# rpm.net
KiCad netlist of a schematic drawn in Altium Designer
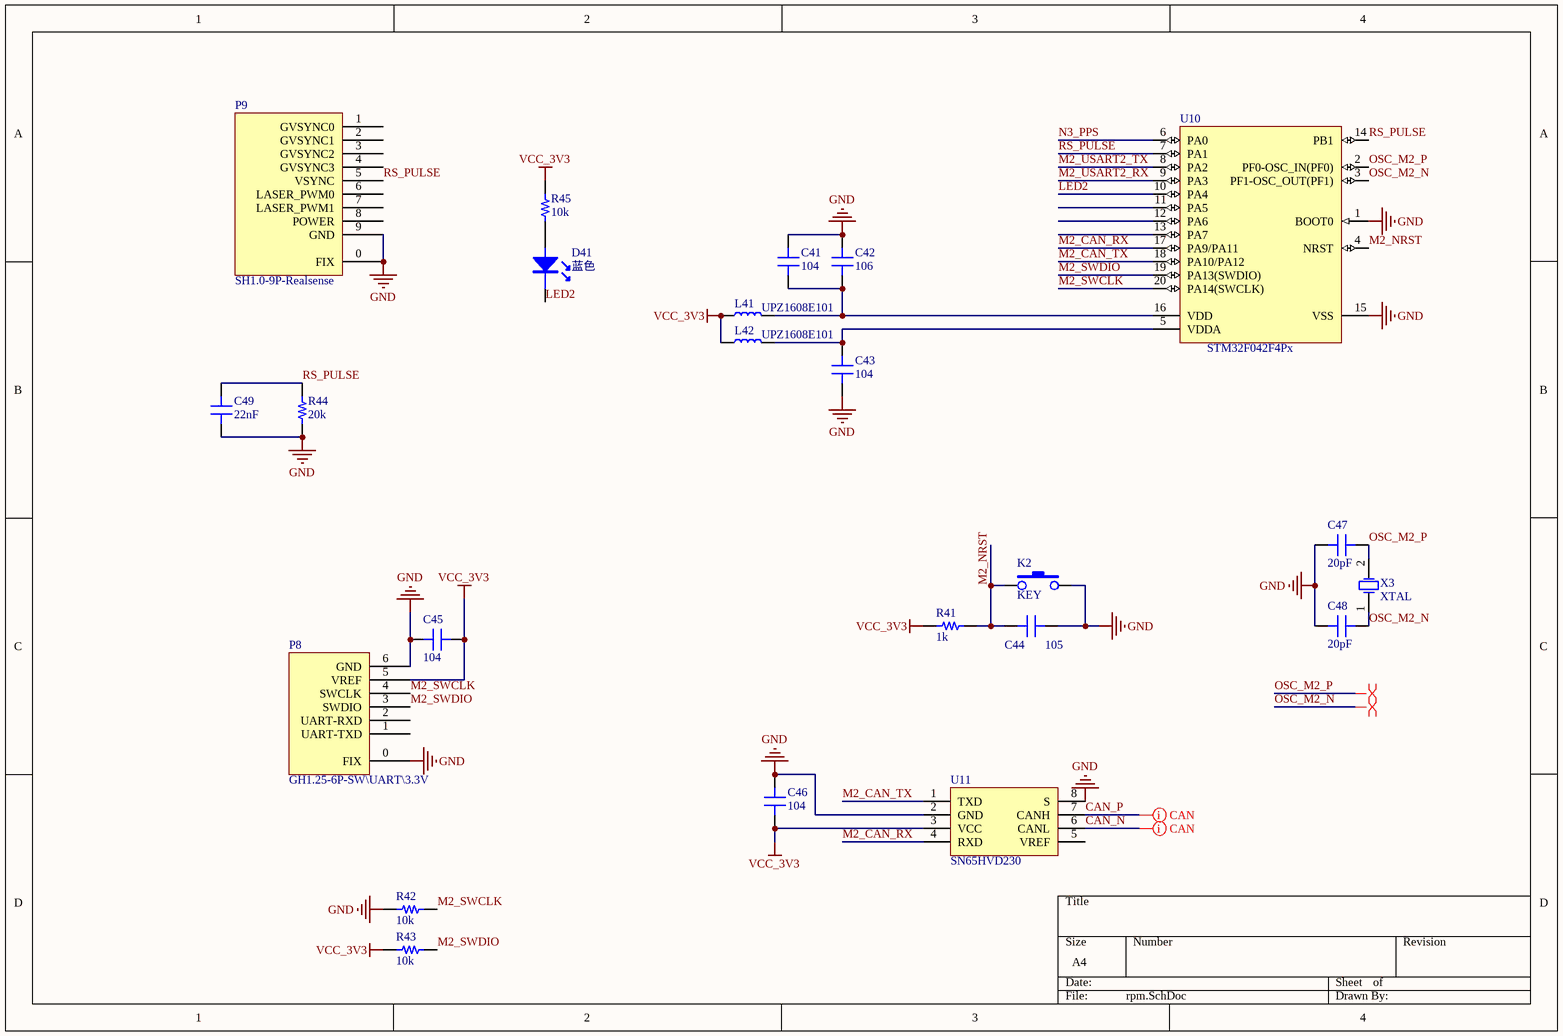
[diagram p0: rpm.SchDoc]

(export (version "E")
  (design (tool "Eeschema 10.0.6"))
  (components
    (comp (ref "C41")
      (value "104")
      (footprint "C0603/1608")
      (description "陶瓷电容")
      (libsource (lib "WMJ2019_Devices") (part "陶瓷电容"))
    )
    (comp (ref "C42")
      (value "106")
      (footprint "C0603/1608")
      (description "陶瓷电容")
      (libsource (lib "WMJ2019_Devices") (part "陶瓷电容"))
    )
    (comp (ref "C43")
      (value "104")
      (footprint "C0603/1608")
      (description "陶瓷电容")
      (libsource (lib "WMJ2019_Devices") (part "陶瓷电容"))
    )
    (comp (ref "C44")
      (value "105")
      (footprint "C0603/1608")
      (description "陶瓷电容")
      (libsource (lib "WMJ2019_Devices") (part "陶瓷电容"))
    )
    (comp (ref "C45")
      (value "104")
      (footprint "C0603/1608")
      (description "陶瓷电容")
      (libsource (lib "WMJ2019_Devices") (part "陶瓷电容"))
    )
    (comp (ref "C46")
      (value "104")
      (footprint "C0603/1608")
      (description "陶瓷电容")
      (libsource (lib "WMJ2019_Devices") (part "陶瓷电容"))
    )
    (comp (ref "C47")
      (value "20pF")
      (footprint "C0603/1608")
      (description "陶瓷电容")
      (libsource (lib "Devices") (part "陶瓷电容"))
    )
    (comp (ref "C48")
      (value "20pF")
      (footprint "C0603/1608")
      (description "陶瓷电容")
      (libsource (lib "Devices") (part "陶瓷电容"))
    )
    (comp (ref "C49")
      (value "22nF")
      (footprint "C0603/1608")
      (description "陶瓷电容")
      (libsource (lib "Devices") (part "陶瓷电容"))
    )
    (comp (ref "D41")
      (value "LED-蓝色")
      (footprint "LED0603-蓝色")
      (description "发光二极管")
      (fields (field (name "COLOR") "蓝色"))
      (libsource (lib "Devices") (part "LED"))
    )
    (comp (ref "K2")
      (value "KEY")
      (footprint "按键（2脚）")
      (description "按键-2脚贴片")
      (libsource (lib "Devices") (part "按键（2脚）"))
    )
    (comp (ref "L41")
      (value "UPZ1608E101")
      (footprint "L0603/1608")
      (description "贴片磁珠")
      (libsource (lib "WMJ2019_Devices") (part "磁珠"))
    )
    (comp (ref "L42")
      (value "UPZ1608E101")
      (footprint "L0603/1608")
      (description "贴片磁珠")
      (libsource (lib "WMJ2019_Devices") (part "磁珠"))
    )
    (comp (ref "P8")
      (value "GH1.25-6P-S~{W}UAR~{T}3.3V")
      (footprint "GH1.25-6P（立贴）")
      (description "GH1.25-6P-SW\\UART\\3.3V")
      (libsource (lib "Connectors") (part "GH1.25-6P-SW{backslash}UART{backslash}3.3V"))
    )
    (comp (ref "P9")
      (value "SH1.0-9P-Realsense")
      (footprint "FPC1.0-2H-WS-9P")
      (libsource (lib "Connectors") (part "SH1.0-9P-Realsense"))
    )
    (comp (ref "R41")
      (value "1k")
      (footprint "R0603/1608")
      (description "电阻")
      (libsource (lib "WMJ2019_Devices") (part "电阻"))
    )
    (comp (ref "R42")
      (value "10k")
      (footprint "R0603/1608")
      (description "电阻")
      (libsource (lib "WMJ2019_Devices") (part "电阻"))
    )
    (comp (ref "R43")
      (value "10k")
      (footprint "R0603/1608")
      (description "电阻")
      (libsource (lib "WMJ2019_Devices") (part "电阻"))
    )
    (comp (ref "R44")
      (value "20k")
      (footprint "R0603/1608")
      (description "电阻")
      (libsource (lib "Devices") (part "电阻"))
    )
    (comp (ref "R45")
      (value "10k")
      (footprint "R0603/1608")
      (description "电阻")
      (libsource (lib "WMJ2019_Devices") (part "电阻"))
    )
    (comp (ref "U10")
      (value "STM32F042F4Px")
      (footprint "TSSOP20")
      (libsource (lib "Devices") (part "STM32F042F4Px"))
    )
    (comp (ref "U11")
      (value "SN65HVD230")
      (footprint "SOP-8")
      (description "CAN收发芯片")
      (libsource (lib "WMJ2019_Devices") (part "SN65HVD230"))
    )
    (comp (ref "X3")
      (value "XTAL")
      (footprint "XTAL-49S")
      (description "晶振")
      (fields (field (name "PUBLISHER") "Altium Limited"))
      (libsource (lib "Devices") (part "晶振"))
    )
  )
  (nets
    (net (code "1") (name "/CAN_N") (class "Default")
      (node (ref "U11") (pin "6") (pinfunction "CANL_6") (pintype "passive"))
    )
    (net (code "2") (name "/CAN_P") (class "Default")
      (node (ref "U11") (pin "7") (pinfunction "CANH_7") (pintype "passive"))
    )
    (net (code "3") (name "/LED2") (class "Default")
      (node (ref "D41") (pin "2") (pinfunction "K_2") (pintype "passive"))
      (node (ref "U10") (pin "10") (pinfunction "PA4_10") (pintype "bidirectional"))
    )
    (net (code "4") (name "/M2_CAN_RX") (class "Default")
      (node (ref "U10") (pin "17") (pinfunction "PA9/PA11_17") (pintype "bidirectional"))
      (node (ref "U11") (pin "4") (pinfunction "RXD_4") (pintype "passive"))
    )
    (net (code "5") (name "/M2_CAN_TX") (class "Default")
      (node (ref "U10") (pin "18") (pinfunction "PA10/PA12_18") (pintype "bidirectional"))
      (node (ref "U11") (pin "1") (pinfunction "TXD_1") (pintype "passive"))
    )
    (net (code "6") (name "/M2_NRST") (class "Default")
      (node (ref "C44") (pin "2") (pintype "passive"))
      (node (ref "K2") (pin "1") (pintype "passive"))
      (node (ref "R41") (pin "2") (pintype "passive"))
      (node (ref "U10") (pin "4") (pinfunction "NRST_4") (pintype "bidirectional"))
    )
    (net (code "7") (name "/M2_SWCLK") (class "Default")
      (node (ref "P8") (pin "4") (pinfunction "SWCLK_4") (pintype "passive"))
      (node (ref "R42") (pin "2") (pintype "passive"))
      (node (ref "U10") (pin "20") (pinfunction "PA14(SWCLK)_20") (pintype "bidirectional"))
    )
    (net (code "8") (name "/M2_SWDIO") (class "Default")
      (node (ref "P8") (pin "3") (pinfunction "SWDIO_3") (pintype "passive"))
      (node (ref "R43") (pin "2") (pintype "passive"))
      (node (ref "U10") (pin "19") (pinfunction "PA13(SWDIO)_19") (pintype "bidirectional"))
    )
    (net (code "9") (name "/M2_USART2_RX") (class "Default")
      (node (ref "U10") (pin "9") (pinfunction "PA3_9") (pintype "bidirectional"))
    )
    (net (code "10") (name "/M2_USART2_TX") (class "Default")
      (node (ref "U10") (pin "8") (pinfunction "PA2_8") (pintype "bidirectional"))
    )
    (net (code "11") (name "/N3_PPS") (class "Default")
      (node (ref "U10") (pin "6") (pinfunction "PA0_6") (pintype "bidirectional"))
    )
    (net (code "12") (name "/OSC_M2_N") (class "Default")
      (node (ref "C48") (pin "1") (pintype "passive"))
      (node (ref "U10") (pin "3") (pinfunction "PF1-OSC_OUT(PF1)_3") (pintype "bidirectional"))
      (node (ref "X3") (pin "1") (pinfunction "OSC1_1") (pintype "passive"))
    )
    (net (code "13") (name "/OSC_M2_P") (class "Default")
      (node (ref "C47") (pin "1") (pintype "passive"))
      (node (ref "U10") (pin "2") (pinfunction "PF0-OSC_IN(PF0)_2") (pintype "bidirectional"))
      (node (ref "X3") (pin "2") (pinfunction "OSC2_2") (pintype "passive"))
    )
    (net (code "14") (name "/RS_PULSE") (class "Default")
      (node (ref "C49") (pin "1") (pintype "passive"))
      (node (ref "P9") (pin "5") (pinfunction "VSYNC_5") (pintype "passive"))
      (node (ref "R44") (pin "2") (pintype "passive"))
      (node (ref "U10") (pin "14") (pinfunction "PB1_14") (pintype "bidirectional"))
      (node (ref "U10") (pin "7") (pinfunction "PA1_7") (pintype "bidirectional"))
    )
    (net (code "15") (name "GND") (class "Default")
      (node (ref "C41") (pin "1") (pintype "passive"))
      (node (ref "C42") (pin "1") (pintype "passive"))
      (node (ref "C43") (pin "1") (pintype "passive"))
      (node (ref "C44") (pin "1") (pintype "passive"))
      (node (ref "C45") (pin "2") (pintype "passive"))
      (node (ref "C46") (pin "2") (pintype "passive"))
      (node (ref "C47") (pin "2") (pintype "passive"))
      (node (ref "C48") (pin "2") (pintype "passive"))
      (node (ref "C49") (pin "2") (pintype "passive"))
      (node (ref "K2") (pin "2") (pintype "passive"))
      (node (ref "P8") (pin "0") (pinfunction "FIX_0") (pintype "passive"))
      (node (ref "P8") (pin "6") (pinfunction "GND_6") (pintype "passive"))
      (node (ref "P9") (pin "0") (pinfunction "FIX_0") (pintype "passive"))
      (node (ref "P9") (pin "9") (pinfunction "GND_9") (pintype "passive"))
      (node (ref "R42") (pin "1") (pintype "passive"))
      (node (ref "R44") (pin "1") (pintype "passive"))
      (node (ref "U10") (pin "1") (pinfunction "BOOT0_1") (pintype "input"))
      (node (ref "U10") (pin "15") (pinfunction "VSS_15") (pintype "power_in"))
      (node (ref "U11") (pin "2") (pinfunction "GND_2") (pintype "passive"))
      (node (ref "U11") (pin "8") (pinfunction "S_8") (pintype "passive"))
    )
    (net (code "16") (name "Net-(D41-A)") (class "Default")
      (node (ref "D41") (pin "1") (pinfunction "A_1") (pintype "passive"))
      (node (ref "R45") (pin "1") (pintype "passive"))
    )
    (net (code "17") (name "Net-(U10-VDD)") (class "Default")
      (node (ref "C41") (pin "2") (pintype "passive"))
      (node (ref "C42") (pin "2") (pintype "passive"))
      (node (ref "L41") (pin "2") (pinfunction "2_2") (pintype "passive"))
      (node (ref "U10") (pin "16") (pinfunction "VDD_16") (pintype "power_in"))
    )
    (net (code "18") (name "Net-(U10-VDDA)") (class "Default")
      (node (ref "C43") (pin "2") (pintype "passive"))
      (node (ref "L42") (pin "2") (pinfunction "2_2") (pintype "passive"))
      (node (ref "U10") (pin "5") (pinfunction "VDDA_5") (pintype "power_in"))
    )
    (net (code "19") (name "VCC_3V3") (class "Default")
      (node (ref "C45") (pin "1") (pintype "passive"))
      (node (ref "C46") (pin "1") (pintype "passive"))
      (node (ref "L41") (pin "1") (pinfunction "1_1") (pintype "passive"))
      (node (ref "L42") (pin "1") (pinfunction "1_1") (pintype "passive"))
      (node (ref "P8") (pin "5") (pinfunction "VREF_5") (pintype "passive"))
      (node (ref "R41") (pin "1") (pintype "passive"))
      (node (ref "R43") (pin "1") (pintype "passive"))
      (node (ref "R45") (pin "2") (pintype "passive"))
      (node (ref "U11") (pin "3") (pinfunction "VCC_3") (pintype "passive"))
    )
    (net (code "20") (name "unconnected-(P8-UART-RXD-Pad2)") (class "Default")
      (node (ref "P8") (pin "2") (pinfunction "UART-RXD_2") (pintype "passive"))
    )
    (net (code "21") (name "unconnected-(P8-UART-TXD-Pad1)") (class "Default")
      (node (ref "P8") (pin "1") (pinfunction "UART-TXD_1") (pintype "passive"))
    )
    (net (code "22") (name "unconnected-(P9-GVSYNC0-Pad1)") (class "Default")
      (node (ref "P9") (pin "1") (pinfunction "GVSYNC0_1") (pintype "passive"))
    )
    (net (code "23") (name "unconnected-(P9-GVSYNC1-Pad2)") (class "Default")
      (node (ref "P9") (pin "2") (pinfunction "GVSYNC1_2") (pintype "passive"))
    )
    (net (code "24") (name "unconnected-(P9-GVSYNC2-Pad3)") (class "Default")
      (node (ref "P9") (pin "3") (pinfunction "GVSYNC2_3") (pintype "passive"))
    )
    (net (code "25") (name "unconnected-(P9-GVSYNC3-Pad4)") (class "Default")
      (node (ref "P9") (pin "4") (pinfunction "GVSYNC3_4") (pintype "passive"))
    )
    (net (code "26") (name "unconnected-(P9-LASER_PWM0-Pad6)") (class "Default")
      (node (ref "P9") (pin "6") (pinfunction "LASER_PWM0_6") (pintype "passive"))
    )
    (net (code "27") (name "unconnected-(P9-LASER_PWM1-Pad7)") (class "Default")
      (node (ref "P9") (pin "7") (pinfunction "LASER_PWM1_7") (pintype "passive"))
    )
    (net (code "28") (name "unconnected-(P9-POWER-Pad8)") (class "Default")
      (node (ref "P9") (pin "8") (pinfunction "POWER_8") (pintype "passive"))
    )
    (net (code "29") (name "unconnected-(U10-PA5-Pad11)") (class "Default")
      (node (ref "U10") (pin "11") (pinfunction "PA5_11") (pintype "bidirectional"))
    )
    (net (code "30") (name "unconnected-(U10-PA6-Pad12)") (class "Default")
      (node (ref "U10") (pin "12") (pinfunction "PA6_12") (pintype "bidirectional"))
    )
    (net (code "31") (name "unconnected-(U10-PA7-Pad13)") (class "Default")
      (node (ref "U10") (pin "13") (pinfunction "PA7_13") (pintype "bidirectional"))
    )
    (net (code "32") (name "unconnected-(U11-VREF-Pad5)") (class "Default")
      (node (ref "U11") (pin "5") (pinfunction "VREF_5") (pintype "passive"))
    )
  )
)
